# FMC_PCIe_Carrier.net
KiCad netlist of a schematic drawn in Altium Designer
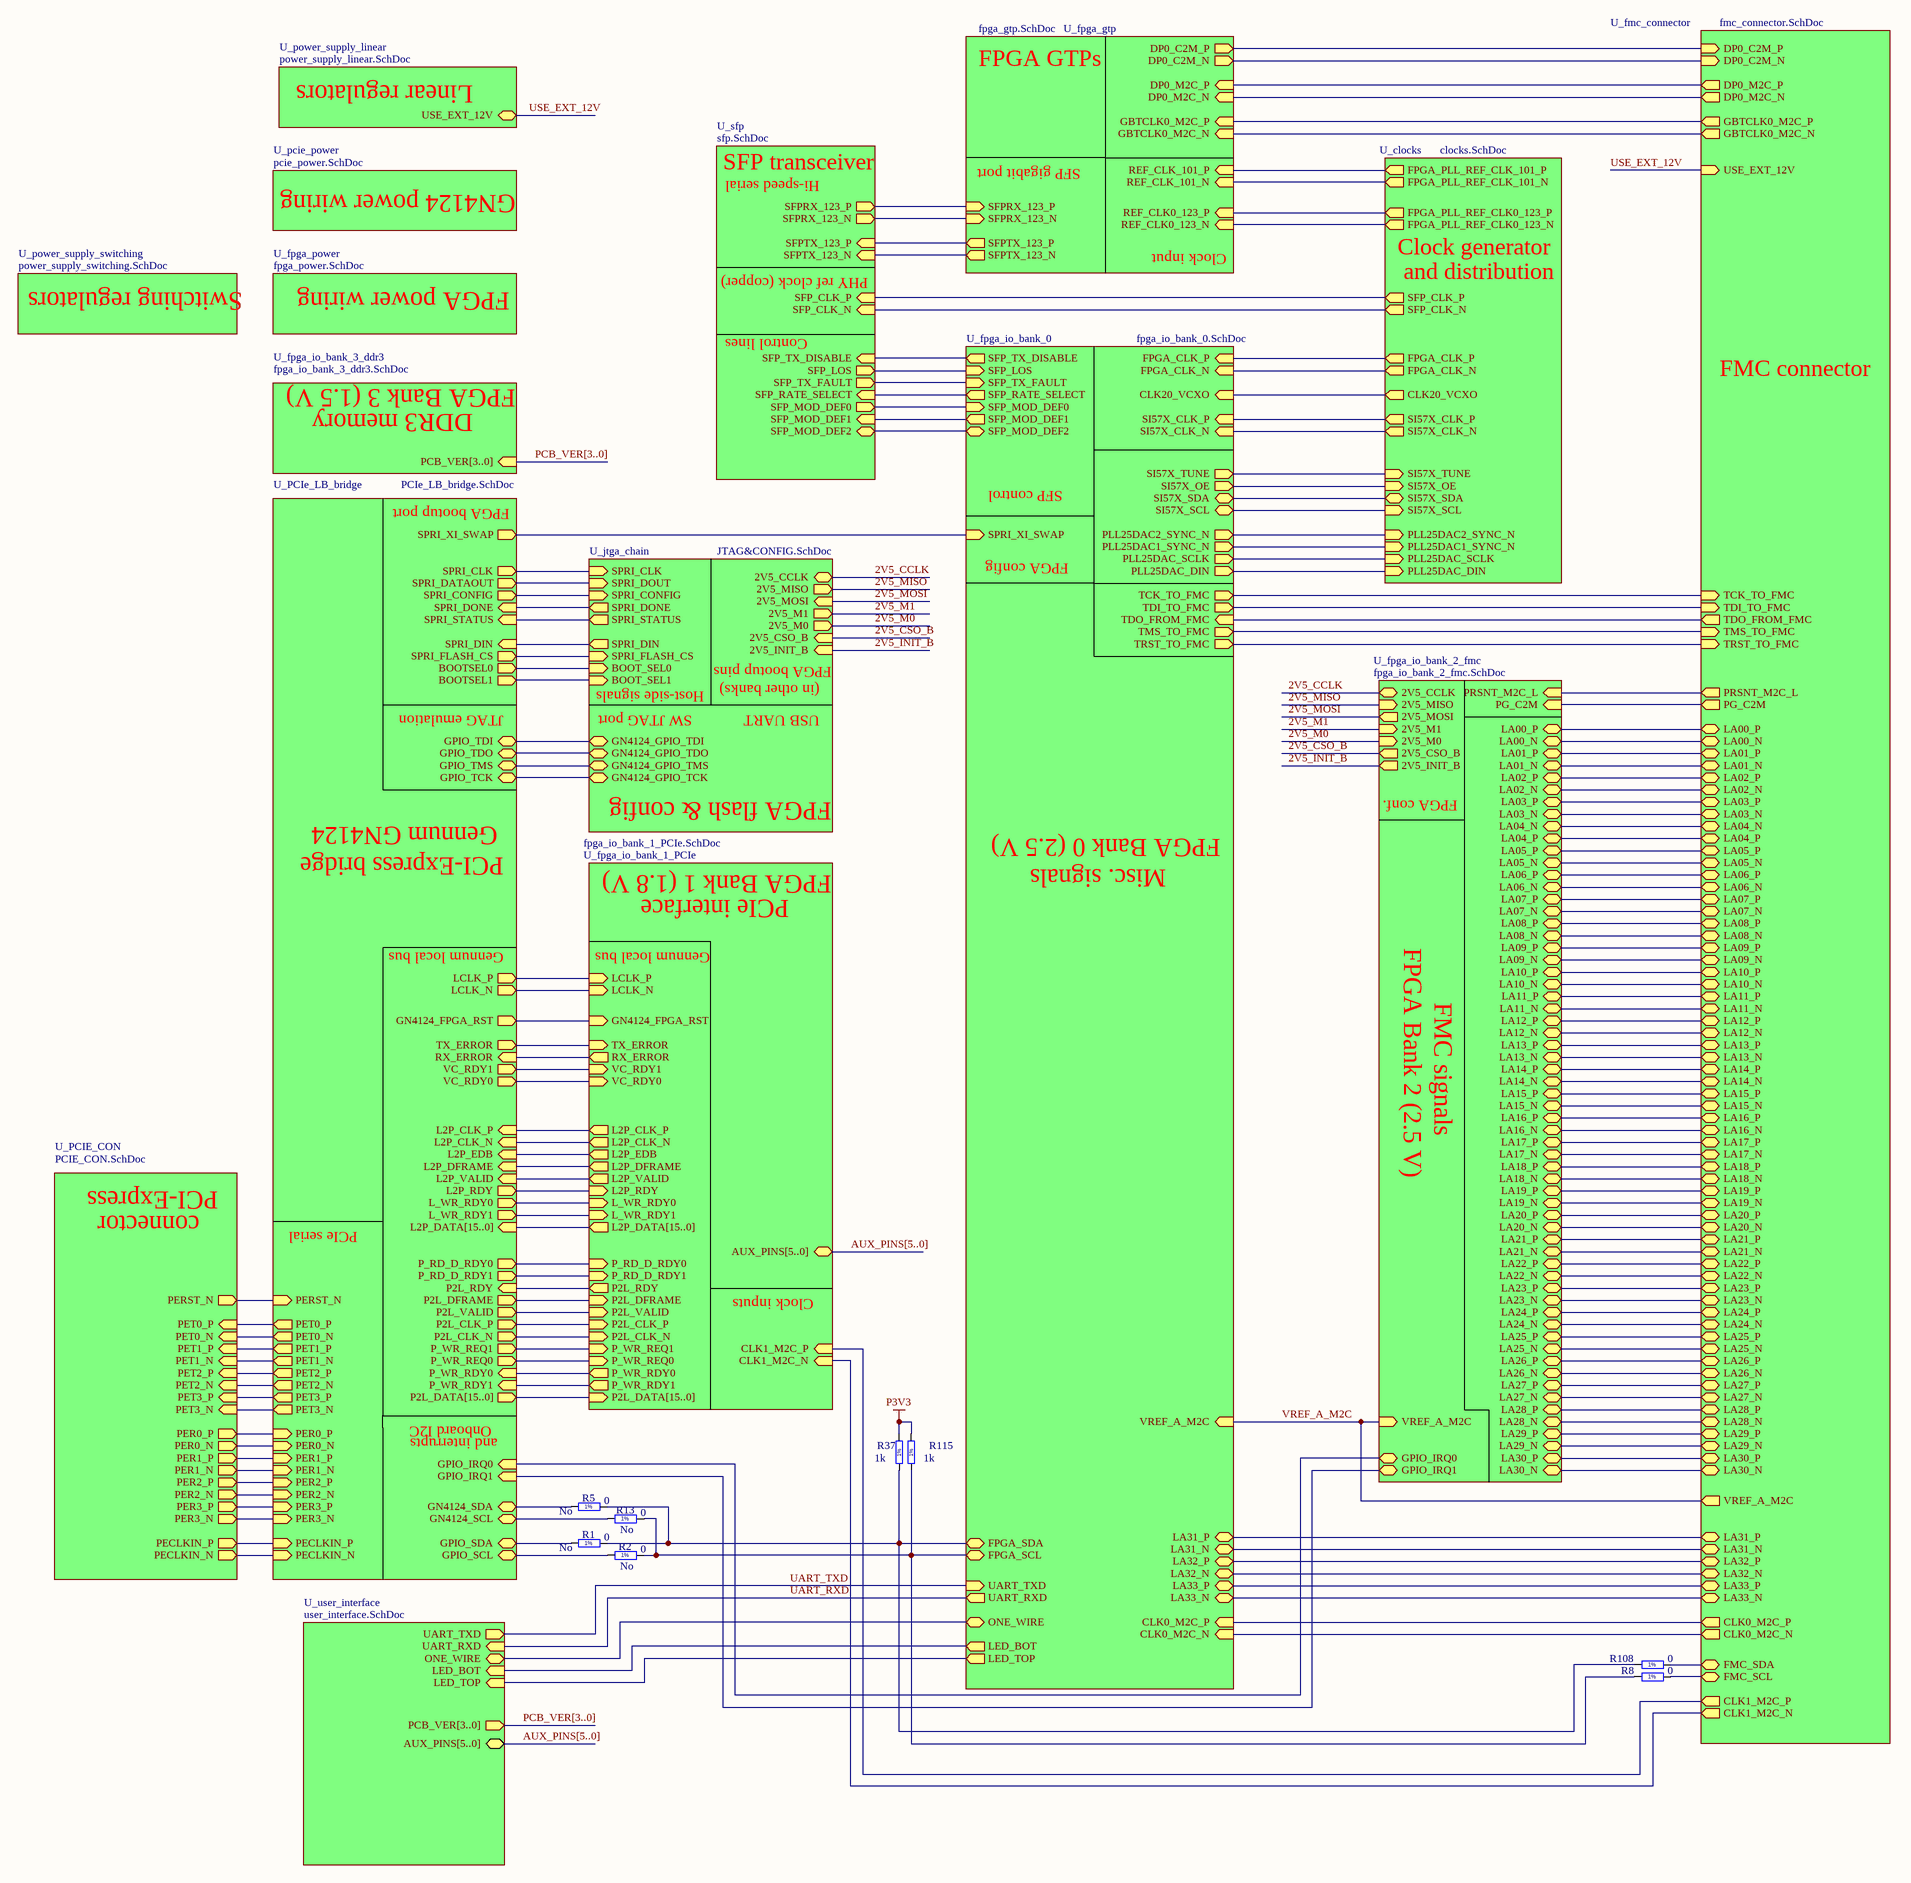
[diagram p0: FMC_PCIe_Carrier.SchDoc]

(export (version "E")
  (design (tool "Eeschema 10.0.6"))
  (components
    (comp (ref "R1")
      (value "0")
      (footprint "RESC1608X55N")
      (description "Resistor - 1%")
      (fields
        (field (name "PART NUMBER") "R0603_0R_JUMPER")
        (field (name "MANUFACTURER") "GENERIC")
        (field (name "MOUNTED") "No")
        (field (name "AUTHOR") "CERN DEM JLC")
      )
      (libsource (lib "Resistors") (part "Resistor - 1%"))
    )
    (comp (ref "R2")
      (value "0")
      (footprint "RESC1608X55N")
      (description "Resistor - 1%")
      (fields
        (field (name "PART NUMBER") "R0603_0R_JUMPER")
        (field (name "MANUFACTURER") "GENERIC")
        (field (name "MOUNTED") "No")
        (field (name "AUTHOR") "CERN DEM JLC")
      )
      (libsource (lib "Resistors") (part "Resistor - 1%"))
    )
    (comp (ref "R5")
      (value "0")
      (footprint "RESC1608X55N")
      (description "Resistor - 1%")
      (fields
        (field (name "PART NUMBER") "R0603_0R_JUMPER")
        (field (name "MANUFACTURER") "GENERIC")
        (field (name "MOUNTED") "No")
        (field (name "AUTHOR") "CERN DEM JLC")
      )
      (libsource (lib "Resistors") (part "Resistor - 1%"))
    )
    (comp (ref "R8")
      (value "0")
      (footprint "RESC1608X55N")
      (description "Resistor - 1%")
      (fields
        (field (name "PART NUMBER") "R0603_0R_JUMPER")
        (field (name "MANUFACTURER") "GENERIC")
        (field (name "AUTHOR") "CERN DEM JLC")
      )
      (libsource (lib "Resistors") (part "Resistor - 1%"))
    )
    (comp (ref "R13")
      (value "0")
      (footprint "RESC1608X55N")
      (description "Resistor - 1%")
      (fields
        (field (name "PART NUMBER") "R0603_0R_JUMPER")
        (field (name "MANUFACTURER") "GENERIC")
        (field (name "MOUNTED") "No")
        (field (name "AUTHOR") "CERN DEM JLC")
      )
      (libsource (lib "Resistors") (part "Resistor - 1%"))
    )
    (comp (ref "R37")
      (value "1k")
      (footprint "RESC1608X55N")
      (description "Resistor - 1%")
      (fields
        (field (name "PART NUMBER") "R0603_1K_1%_0.1W_100PPM")
        (field (name "POWER") "0.1W")
        (field (name "AUTHOR") "CERN DEM JLC")
      )
      (libsource (lib "Resistors") (part "Resistor - 1%"))
    )
    (comp (ref "R108")
      (value "0")
      (footprint "RESC1608X55N")
      (description "Resistor - 1%")
      (fields
        (field (name "PART NUMBER") "R0603_0R_JUMPER")
        (field (name "MANUFACTURER") "GENERIC")
        (field (name "AUTHOR") "CERN DEM JLC")
      )
      (libsource (lib "Resistors") (part "Resistor - 1%"))
    )
    (comp (ref "R115")
      (value "1k")
      (footprint "RESC1608X55N")
      (description "Resistor - 1%")
      (fields
        (field (name "PART NUMBER") "R0603_1K_1%_0.1W_100PPM")
        (field (name "POWER") "0.1W")
        (field (name "AUTHOR") "CERN DEM JLC")
      )
      (libsource (lib "Resistors") (part "Resistor - 1%"))
    )
  )
  (nets
    (net (code "30") (name "/FMC_SCL") (class "Default")
      (node (ref "R8") (pin "2") (pinfunction "2_2") (pintype "passive"))
    )
    (net (code "31") (name "/FMC_SDA") (class "Default")
      (node (ref "R108") (pin "2") (pinfunction "2_2") (pintype "passive"))
    )
    (net (code "38") (name "/FPGA_SCL") (class "Default")
      (node (ref "R115") (pin "1") (pinfunction "1_1") (pintype "passive"))
      (node (ref "R13") (pin "2") (pinfunction "2_2") (pintype "passive"))
      (node (ref "R2") (pin "2") (pinfunction "2_2") (pintype "passive"))
      (node (ref "R8") (pin "1") (pinfunction "1_1") (pintype "passive"))
    )
    (net (code "39") (name "/FPGA_SDA") (class "Default")
      (node (ref "R1") (pin "2") (pinfunction "2_2") (pintype "passive"))
      (node (ref "R108") (pin "1") (pinfunction "1_1") (pintype "passive"))
      (node (ref "R37") (pin "1") (pinfunction "1_1") (pintype "passive"))
      (node (ref "R5") (pin "2") (pinfunction "2_2") (pintype "passive"))
    )
    (net (code "47") (name "/GN4124_SCL") (class "Default")
      (node (ref "R13") (pin "1") (pinfunction "1_1") (pintype "passive"))
    )
    (net (code "48") (name "/GN4124_SDA") (class "Default")
      (node (ref "R5") (pin "1") (pinfunction "1_1") (pintype "passive"))
    )
    (net (code "51") (name "/GPIO_SCL") (class "Default")
      (node (ref "R2") (pin "1") (pinfunction "1_1") (pintype "passive"))
    )
    (net (code "52") (name "/GPIO_SDA") (class "Default")
      (node (ref "R1") (pin "1") (pinfunction "1_1") (pintype "passive"))
    )
    (net (code "213") (name "P3V3") (class "Default")
      (node (ref "R115") (pin "2") (pinfunction "2_2") (pintype "passive"))
      (node (ref "R37") (pin "2") (pinfunction "2_2") (pintype "passive"))
    )
  )
)
